# LightSensor.net
KiCad netlist of a schematic drawn in EAGLE
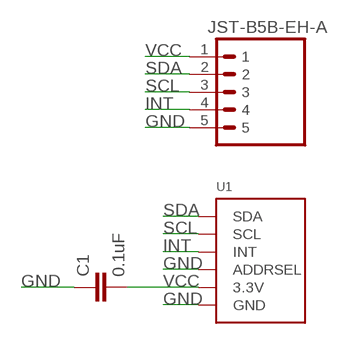
[diagram p0: schematic, sheet 1]

(export (version "E")
  (design (tool "Eeschema 10.0.6"))
  (components
    (comp (ref "C1")
      (value "0.1uF")
      (footprint "eagle-import:0603-CAP")
      (libsource (lib "eagle-import") (part "0.1UF-25V-5%(0603)"))
    )
    (comp (ref "U$1")
      (value "JST-B5B-EH-A")
      (footprint "eagle-import:JST-B5B-ED-A")
      (libsource (lib "eagle-import") (part "JST-B5B-EH-A"))
    )
    (comp (ref "U1")
      (value "LIGHT_TSL2561")
      (footprint "eagle-import:TSL2561_FN")
      (libsource (lib "eagle-import") (part "LIGHT_TSL2561"))
    )
  )
  (nets
    (net (code "1") (name "/GND") (class "Default")
      (node (ref "C1") (pin "1") (pinfunction "1_1") (pintype "passive"))
      (node (ref "U$1") (pin "5") (pinfunction "5_5") (pintype "bidirectional"))
      (node (ref "U1") (pin "ADR") (pinfunction "ADDRSEL_ADR") (pintype "bidirectional"))
      (node (ref "U1") (pin "VSS") (pinfunction "GND_VSS") (pintype "bidirectional"))
    )
    (net (code "2") (name "/INT") (class "Default")
      (node (ref "U$1") (pin "4") (pinfunction "4_4") (pintype "bidirectional"))
      (node (ref "U1") (pin "INT") (pinfunction "INT_INT") (pintype "bidirectional"))
    )
    (net (code "3") (name "/SCL") (class "Default")
      (node (ref "U$1") (pin "3") (pinfunction "3_3") (pintype "bidirectional"))
      (node (ref "U1") (pin "CLK") (pinfunction "SCL_CLK") (pintype "bidirectional"))
    )
    (net (code "4") (name "/SDA") (class "Default")
      (node (ref "U$1") (pin "2") (pinfunction "2_2") (pintype "bidirectional"))
      (node (ref "U1") (pin "DATA") (pinfunction "SDA_DATA") (pintype "bidirectional"))
    )
    (net (code "5") (name "/VCC") (class "Default")
      (node (ref "C1") (pin "2") (pinfunction "2_2") (pintype "passive"))
      (node (ref "U$1") (pin "1") (pinfunction "1_1") (pintype "bidirectional"))
      (node (ref "U1") (pin "VDD") (pinfunction "3.3V_VDD") (pintype "bidirectional"))
    )
  )
)
